# 6packRev3A.net
KiCad netlist of a schematic drawn in EAGLE
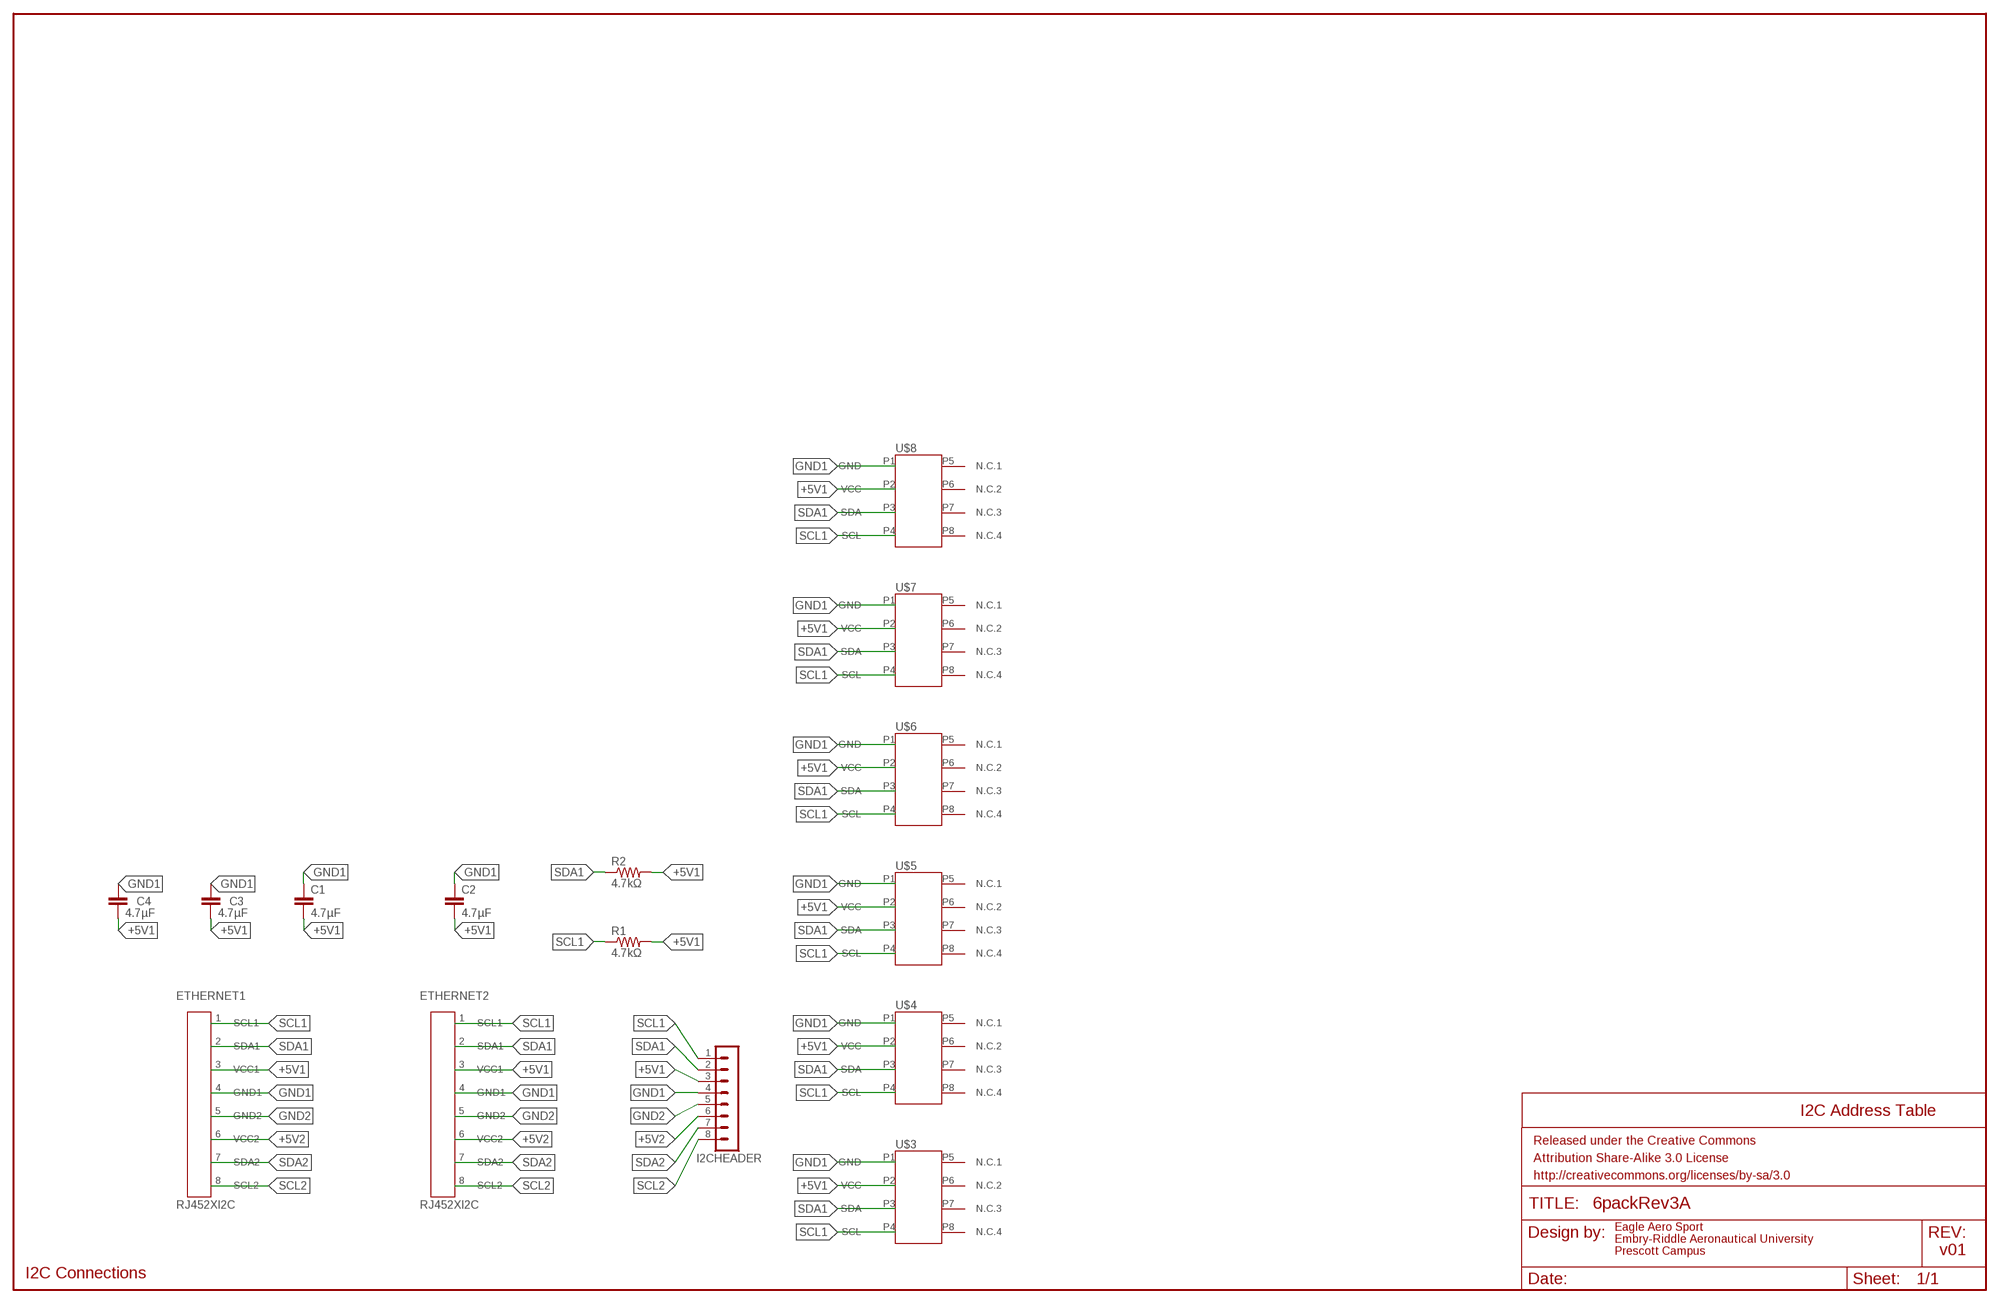
[diagram p0: schematic, sheet 1]

(export (version "E")
  (design (tool "Eeschema 10.0.6"))
  (components
    (comp (ref "C1")
      (value "4.7µF")
      (footprint "eagle-import:0805")
      (libsource (lib "eagle-import") (part "0.33UF/330NF-0805-50V-10%"))
    )
    (comp (ref "C2")
      (value "4.7µF")
      (footprint "eagle-import:0805")
      (libsource (lib "eagle-import") (part "0.33UF/330NF-0805-50V-10%"))
    )
    (comp (ref "C3")
      (value "4.7µF")
      (footprint "eagle-import:CAP-PTH-10MM")
      (libsource (lib "eagle-import") (part "10NF-PTH-10MM-10000V-1-%"))
    )
    (comp (ref "C4")
      (value "4.7µF")
      (footprint "eagle-import:CAP-PTH-10MM")
      (libsource (lib "eagle-import") (part "10NF-PTH-10MM-10000V-1-%"))
    )
    (comp (ref "ETHERNET1")
      (value "RJ452XI2C")
      (footprint "eagle-import:RJ45-8")
      (libsource (lib "eagle-import") (part "RJ452XI2C"))
    )
    (comp (ref "ETHERNET2")
      (value "RJ452XI2C")
      (footprint "eagle-import:RJ45-8")
      (libsource (lib "eagle-import") (part "RJ452XI2C"))
    )
    (comp (ref "FRAME1")
      (value "FRAME-LEDGER")
      (footprint "eagle-import:CREATIVE_COMMONS")
      (libsource (lib "eagle-import") (part "FRAME-LEDGER"))
    )
    (comp (ref "I2CHEADER")
      (value "MA08-1")
      (footprint "eagle-import:MA08-1")
      (libsource (lib "eagle-import") (part "MA08-1"))
    )
    (comp (ref "R1")
      (value "4.7kΩ")
      (footprint "eagle-import:0207_12")
      (libsource (lib "eagle-import") (part "R-US_0207/12"))
    )
    (comp (ref "R2")
      (value "4.7kΩ")
      (footprint "eagle-import:0207_12")
      (libsource (lib "eagle-import") (part "R-US_0207/12"))
    )
    (comp (ref "U$3")
      (value "AMS5915")
      (footprint "eagle-import:DIP8W")
      (libsource (lib "eagle-import") (part "AMS5915"))
    )
    (comp (ref "U$4")
      (value "AMS5915")
      (footprint "eagle-import:DIP8W")
      (libsource (lib "eagle-import") (part "AMS5915"))
    )
    (comp (ref "U$5")
      (value "AMS5915")
      (footprint "eagle-import:DIP8W")
      (libsource (lib "eagle-import") (part "AMS5915"))
    )
    (comp (ref "U$6")
      (value "AMS5915")
      (footprint "eagle-import:DIP8W")
      (libsource (lib "eagle-import") (part "AMS5915"))
    )
    (comp (ref "U$7")
      (value "AMS5915")
      (footprint "eagle-import:DIP8W")
      (libsource (lib "eagle-import") (part "AMS5915"))
    )
    (comp (ref "U$8")
      (value "AMS5915")
      (footprint "eagle-import:DIP8W")
      (libsource (lib "eagle-import") (part "AMS5915"))
    )
  )
  (nets
    (net (code "1") (name "+5V1") (class "Default")
      (node (ref "C1") (pin "2") (pinfunction "2_2") (pintype "passive"))
      (node (ref "C2") (pin "2") (pinfunction "2_2") (pintype "passive"))
      (node (ref "C3") (pin "2") (pinfunction "2_2") (pintype "passive"))
      (node (ref "C4") (pin "2") (pinfunction "2_2") (pintype "passive"))
      (node (ref "ETHERNET1") (pin "3") (pinfunction "VCC1_3") (pintype "bidirectional"))
      (node (ref "ETHERNET2") (pin "3") (pinfunction "VCC1_3") (pintype "bidirectional"))
      (node (ref "I2CHEADER") (pin "3") (pinfunction "3_3") (pintype "passive"))
      (node (ref "R1") (pin "2") (pinfunction "2_2") (pintype "passive"))
      (node (ref "R2") (pin "2") (pinfunction "2_2") (pintype "passive"))
      (node (ref "U$3") (pin "P2") (pinfunction "VCC_P2") (pintype "power_in"))
      (node (ref "U$4") (pin "P2") (pinfunction "VCC_P2") (pintype "power_in"))
      (node (ref "U$5") (pin "P2") (pinfunction "VCC_P2") (pintype "power_in"))
      (node (ref "U$6") (pin "P2") (pinfunction "VCC_P2") (pintype "power_in"))
      (node (ref "U$7") (pin "P2") (pinfunction "VCC_P2") (pintype "power_in"))
      (node (ref "U$8") (pin "P2") (pinfunction "VCC_P2") (pintype "power_in"))
    )
    (net (code "2") (name "+5V2") (class "Default")
      (node (ref "ETHERNET1") (pin "6") (pinfunction "VCC2_6") (pintype "bidirectional"))
      (node (ref "ETHERNET2") (pin "6") (pinfunction "VCC2_6") (pintype "bidirectional"))
      (node (ref "I2CHEADER") (pin "6") (pinfunction "6_6") (pintype "passive"))
    )
    (net (code "3") (name "GND1") (class "Default")
      (node (ref "C1") (pin "1") (pinfunction "1_1") (pintype "passive"))
      (node (ref "C2") (pin "1") (pinfunction "1_1") (pintype "passive"))
      (node (ref "C3") (pin "1") (pinfunction "1_1") (pintype "passive"))
      (node (ref "C4") (pin "1") (pinfunction "1_1") (pintype "passive"))
      (node (ref "ETHERNET1") (pin "4") (pinfunction "GND1_4") (pintype "bidirectional"))
      (node (ref "ETHERNET2") (pin "4") (pinfunction "GND1_4") (pintype "bidirectional"))
      (node (ref "I2CHEADER") (pin "4") (pinfunction "4_4") (pintype "passive"))
      (node (ref "U$3") (pin "P1") (pinfunction "GND_P1") (pintype "bidirectional"))
      (node (ref "U$4") (pin "P1") (pinfunction "GND_P1") (pintype "bidirectional"))
      (node (ref "U$5") (pin "P1") (pinfunction "GND_P1") (pintype "bidirectional"))
      (node (ref "U$6") (pin "P1") (pinfunction "GND_P1") (pintype "bidirectional"))
      (node (ref "U$7") (pin "P1") (pinfunction "GND_P1") (pintype "bidirectional"))
      (node (ref "U$8") (pin "P1") (pinfunction "GND_P1") (pintype "bidirectional"))
    )
    (net (code "4") (name "GND2") (class "Default")
      (node (ref "ETHERNET1") (pin "5") (pinfunction "GND2_5") (pintype "bidirectional"))
      (node (ref "ETHERNET2") (pin "5") (pinfunction "GND2_5") (pintype "bidirectional"))
      (node (ref "I2CHEADER") (pin "5") (pinfunction "5_5") (pintype "passive"))
    )
    (net (code "5") (name "SCL1") (class "Default")
      (node (ref "ETHERNET1") (pin "1") (pinfunction "SCL1_1") (pintype "bidirectional"))
      (node (ref "ETHERNET2") (pin "1") (pinfunction "SCL1_1") (pintype "bidirectional"))
      (node (ref "I2CHEADER") (pin "1") (pinfunction "1_1") (pintype "passive"))
      (node (ref "R1") (pin "1") (pinfunction "1_1") (pintype "passive"))
      (node (ref "U$3") (pin "P4") (pinfunction "SCL_P4") (pintype "bidirectional"))
      (node (ref "U$4") (pin "P4") (pinfunction "SCL_P4") (pintype "bidirectional"))
      (node (ref "U$5") (pin "P4") (pinfunction "SCL_P4") (pintype "bidirectional"))
      (node (ref "U$6") (pin "P4") (pinfunction "SCL_P4") (pintype "bidirectional"))
      (node (ref "U$7") (pin "P4") (pinfunction "SCL_P4") (pintype "bidirectional"))
      (node (ref "U$8") (pin "P4") (pinfunction "SCL_P4") (pintype "bidirectional"))
    )
    (net (code "6") (name "SCL2") (class "Default")
      (node (ref "ETHERNET1") (pin "8") (pinfunction "SCL2_8") (pintype "bidirectional"))
      (node (ref "ETHERNET2") (pin "8") (pinfunction "SCL2_8") (pintype "bidirectional"))
      (node (ref "I2CHEADER") (pin "8") (pinfunction "8_8") (pintype "passive"))
    )
    (net (code "7") (name "SDA1") (class "Default")
      (node (ref "ETHERNET1") (pin "2") (pinfunction "SDA1_2") (pintype "bidirectional"))
      (node (ref "ETHERNET2") (pin "2") (pinfunction "SDA1_2") (pintype "bidirectional"))
      (node (ref "I2CHEADER") (pin "2") (pinfunction "2_2") (pintype "passive"))
      (node (ref "R2") (pin "1") (pinfunction "1_1") (pintype "passive"))
      (node (ref "U$3") (pin "P3") (pinfunction "SDA_P3") (pintype "bidirectional"))
      (node (ref "U$4") (pin "P3") (pinfunction "SDA_P3") (pintype "bidirectional"))
      (node (ref "U$5") (pin "P3") (pinfunction "SDA_P3") (pintype "bidirectional"))
      (node (ref "U$6") (pin "P3") (pinfunction "SDA_P3") (pintype "bidirectional"))
      (node (ref "U$7") (pin "P3") (pinfunction "SDA_P3") (pintype "bidirectional"))
      (node (ref "U$8") (pin "P3") (pinfunction "SDA_P3") (pintype "bidirectional"))
    )
    (net (code "8") (name "SDA2") (class "Default")
      (node (ref "ETHERNET1") (pin "7") (pinfunction "SDA2_7") (pintype "bidirectional"))
      (node (ref "ETHERNET2") (pin "7") (pinfunction "SDA2_7") (pintype "bidirectional"))
      (node (ref "I2CHEADER") (pin "7") (pinfunction "7_7") (pintype "passive"))
    )
    (net (code "9") (name "unconnected-(U$3-N.C.1-PadP5)") (class "Default")
      (node (ref "U$3") (pin "P5") (pinfunction "N.C.1_P5") (pintype "no_connect"))
    )
    (net (code "10") (name "unconnected-(U$3-N.C.2-PadP6)") (class "Default")
      (node (ref "U$3") (pin "P6") (pinfunction "N.C.2_P6") (pintype "no_connect"))
    )
    (net (code "11") (name "unconnected-(U$3-N.C.3-PadP7)") (class "Default")
      (node (ref "U$3") (pin "P7") (pinfunction "N.C.3_P7") (pintype "no_connect"))
    )
    (net (code "12") (name "unconnected-(U$3-N.C.4-PadP8)") (class "Default")
      (node (ref "U$3") (pin "P8") (pinfunction "N.C.4_P8") (pintype "no_connect"))
    )
    (net (code "13") (name "unconnected-(U$4-N.C.1-PadP5)") (class "Default")
      (node (ref "U$4") (pin "P5") (pinfunction "N.C.1_P5") (pintype "no_connect"))
    )
    (net (code "14") (name "unconnected-(U$4-N.C.2-PadP6)") (class "Default")
      (node (ref "U$4") (pin "P6") (pinfunction "N.C.2_P6") (pintype "no_connect"))
    )
    (net (code "15") (name "unconnected-(U$4-N.C.3-PadP7)") (class "Default")
      (node (ref "U$4") (pin "P7") (pinfunction "N.C.3_P7") (pintype "no_connect"))
    )
    (net (code "16") (name "unconnected-(U$4-N.C.4-PadP8)") (class "Default")
      (node (ref "U$4") (pin "P8") (pinfunction "N.C.4_P8") (pintype "no_connect"))
    )
    (net (code "17") (name "unconnected-(U$5-N.C.1-PadP5)") (class "Default")
      (node (ref "U$5") (pin "P5") (pinfunction "N.C.1_P5") (pintype "no_connect"))
    )
    (net (code "18") (name "unconnected-(U$5-N.C.2-PadP6)") (class "Default")
      (node (ref "U$5") (pin "P6") (pinfunction "N.C.2_P6") (pintype "no_connect"))
    )
    (net (code "19") (name "unconnected-(U$5-N.C.3-PadP7)") (class "Default")
      (node (ref "U$5") (pin "P7") (pinfunction "N.C.3_P7") (pintype "no_connect"))
    )
    (net (code "20") (name "unconnected-(U$5-N.C.4-PadP8)") (class "Default")
      (node (ref "U$5") (pin "P8") (pinfunction "N.C.4_P8") (pintype "no_connect"))
    )
    (net (code "21") (name "unconnected-(U$6-N.C.1-PadP5)") (class "Default")
      (node (ref "U$6") (pin "P5") (pinfunction "N.C.1_P5") (pintype "no_connect"))
    )
    (net (code "22") (name "unconnected-(U$6-N.C.2-PadP6)") (class "Default")
      (node (ref "U$6") (pin "P6") (pinfunction "N.C.2_P6") (pintype "no_connect"))
    )
    (net (code "23") (name "unconnected-(U$6-N.C.3-PadP7)") (class "Default")
      (node (ref "U$6") (pin "P7") (pinfunction "N.C.3_P7") (pintype "no_connect"))
    )
    (net (code "24") (name "unconnected-(U$6-N.C.4-PadP8)") (class "Default")
      (node (ref "U$6") (pin "P8") (pinfunction "N.C.4_P8") (pintype "no_connect"))
    )
    (net (code "25") (name "unconnected-(U$7-N.C.1-PadP5)") (class "Default")
      (node (ref "U$7") (pin "P5") (pinfunction "N.C.1_P5") (pintype "no_connect"))
    )
    (net (code "26") (name "unconnected-(U$7-N.C.2-PadP6)") (class "Default")
      (node (ref "U$7") (pin "P6") (pinfunction "N.C.2_P6") (pintype "no_connect"))
    )
    (net (code "27") (name "unconnected-(U$7-N.C.3-PadP7)") (class "Default")
      (node (ref "U$7") (pin "P7") (pinfunction "N.C.3_P7") (pintype "no_connect"))
    )
    (net (code "28") (name "unconnected-(U$7-N.C.4-PadP8)") (class "Default")
      (node (ref "U$7") (pin "P8") (pinfunction "N.C.4_P8") (pintype "no_connect"))
    )
    (net (code "29") (name "unconnected-(U$8-N.C.1-PadP5)") (class "Default")
      (node (ref "U$8") (pin "P5") (pinfunction "N.C.1_P5") (pintype "no_connect"))
    )
    (net (code "30") (name "unconnected-(U$8-N.C.2-PadP6)") (class "Default")
      (node (ref "U$8") (pin "P6") (pinfunction "N.C.2_P6") (pintype "no_connect"))
    )
    (net (code "31") (name "unconnected-(U$8-N.C.3-PadP7)") (class "Default")
      (node (ref "U$8") (pin "P7") (pinfunction "N.C.3_P7") (pintype "no_connect"))
    )
    (net (code "32") (name "unconnected-(U$8-N.C.4-PadP8)") (class "Default")
      (node (ref "U$8") (pin "P8") (pinfunction "N.C.4_P8") (pintype "no_connect"))
    )
  )
)
